# LED.net
KiCad netlist of a schematic drawn in Altium Designer
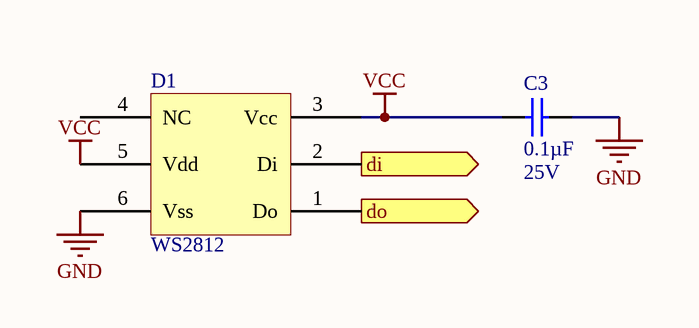
[diagram p0: LED.SchDoc]

(export (version "E")
  (design (tool "Eeschema 10.0.6"))
  (components
    (comp (ref "C3")
      (value "CAP CER .10UF 25V X7R 10% 0603")
      (footprint "0603")
      (fields
        (field (name "MANUFACTURER") "TDK Corporation")
        (field (name "MANUFACTURER PART NUMBER") "C1608X7R1E104K")
        (field (name "TOLERANCE") "±10%")
        (field (name "CAPACITANCE") "0.1µF")
        (field (name "VOLTAGE - RATED") "25V")
      )
      (libsource (lib "parts") (part "CAP_CER_.10UF_25V_X7R_10%_0603_1"))
    )
    (comp (ref "D1") (value "WS2812") (footprint "LED_5050") (libsource (lib "parts") (part "WS2812")))
  )
  (nets
    (net (code "1") (name "/di") (class "Default")
      (node (ref "D1") (pin "2") (pinfunction "Di_2") (pintype "passive"))
    )
    (net (code "2") (name "/do") (class "Default")
      (node (ref "D1") (pin "1") (pinfunction "Do_1") (pintype "passive"))
    )
    (net (code "3") (name "GND") (class "Default")
      (node (ref "C3") (pin "2") (pinfunction "2_2") (pintype "passive"))
      (node (ref "D1") (pin "6") (pinfunction "Vss_6") (pintype "passive"))
    )
    (net (code "4") (name "VCC") (class "Default")
      (node (ref "C3") (pin "1") (pinfunction "1_1") (pintype "passive"))
      (node (ref "D1") (pin "3") (pinfunction "Vcc_3") (pintype "passive"))
      (node (ref "D1") (pin "5") (pinfunction "Vdd_5") (pintype "passive"))
    )
    (net (code "5") (name "unconnected-(D1-NC-Pad4)") (class "Default")
      (node (ref "D1") (pin "4") (pinfunction "NC_4") (pintype "passive"))
    )
  )
)
